# DAC.net
KiCad netlist of a schematic drawn in Altium Designer
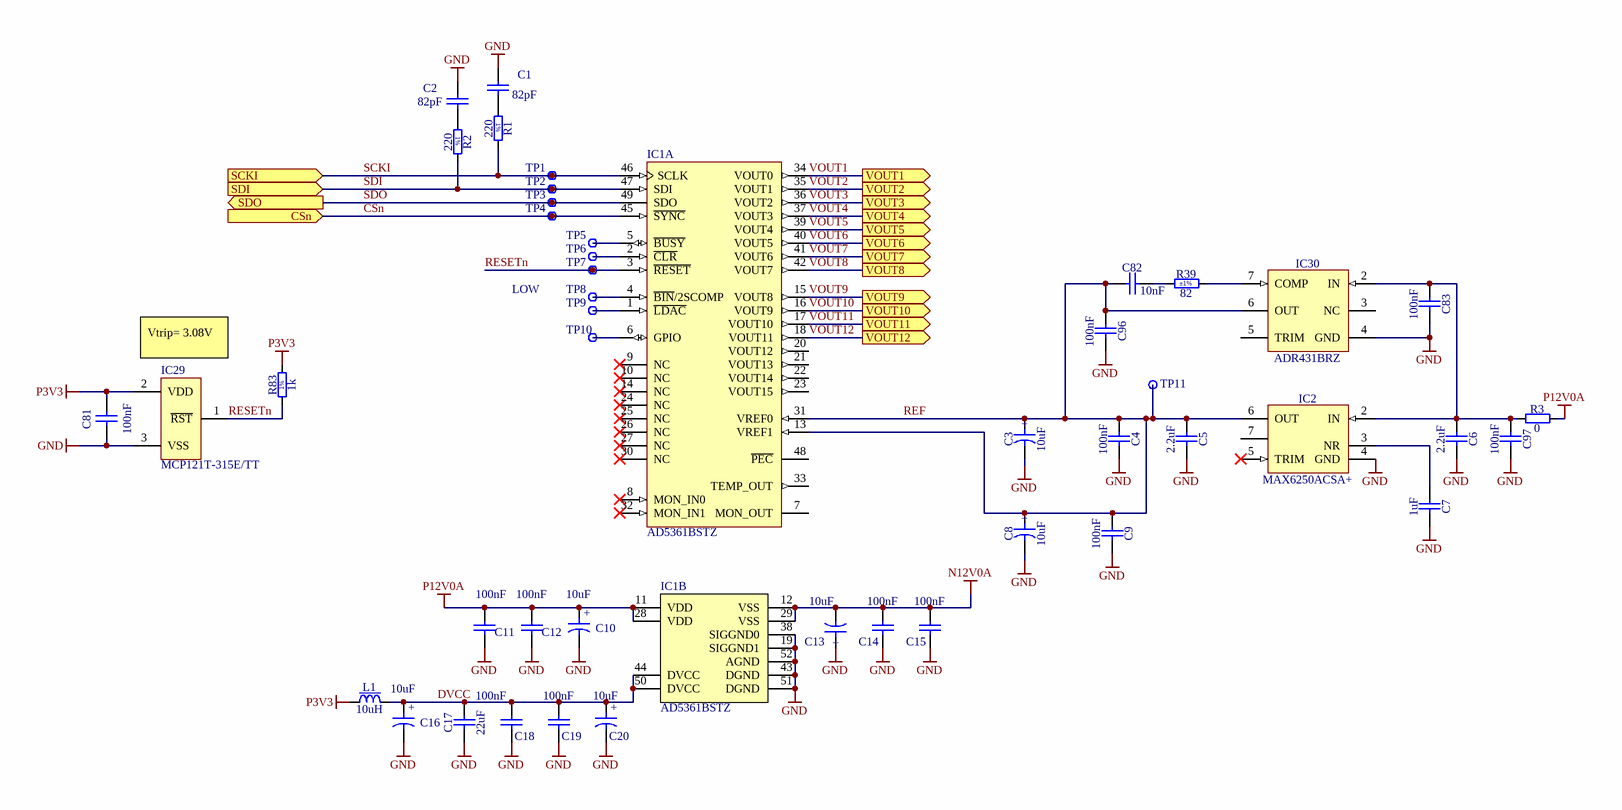
[diagram p0: DAC.SchDoc]

(export (version "E")
  (design (tool "Eeschema 10.0.6"))
  (components
    (comp (ref "C1")
      (value "82pF")
      (footprint "CAPC1608X87N")
      (description "Non-polarised capacitor")
      (fields
        (field (name "PART NUMBER") "CC0603_82PF_50V_5%_NP0")
        (field (name "VOLTAGE") "50V")
        (field (name "AUTHOR") "CERN DEM JLC")
      )
      (libsource (lib "Capacitors") (part "Capacitor - non polarized"))
    )
    (comp (ref "C2")
      (value "82pF")
      (footprint "CAPC1608X87N")
      (description "Non-polarised capacitor")
      (fields
        (field (name "PART NUMBER") "CC0603_82PF_50V_5%_NP0")
        (field (name "VOLTAGE") "50V")
        (field (name "AUTHOR") "CERN DEM JLC")
      )
      (libsource (lib "Capacitors") (part "Capacitor - non polarized"))
    )
    (comp (ref "C3")
      (value "10uF")
      (footprint "CAPMP3216X180N")
      (description "Polarised capacitor")
      (fields
        (field (name "PART NUMBER") "CTE3216-18_10UF_16V_20%_AVX_TCJ")
        (field (name "VOLTAGE") "16V")
        (field (name "AUTHOR") "CERN DEM JLC")
      )
      (libsource (lib "Capacitors") (part "Capacitor - polarized"))
    )
    (comp (ref "C4")
      (value "100nF")
      (footprint "CAPC1005X55N")
      (description "Non-polarised capacitor")
      (fields
        (field (name "PART NUMBER") "CC0402_100NF_16V_10%_X7R")
        (field (name "VOLTAGE") "16V")
        (field (name "AUTHOR") "CERN DEM JLC")
      )
      (libsource (lib "Capacitors") (part "Capacitor - non polarized"))
    )
    (comp (ref "C5")
      (value "2.2uF")
      (footprint "CAPC1608X87N")
      (description "Non-polarised capacitor")
      (fields
        (field (name "PART NUMBER") "CC0603_2.2UF_16V_10%_X5R")
        (field (name "VOLTAGE") "16V")
        (field (name "AUTHOR") "CERN DEM JLC")
      )
      (libsource (lib "Capacitors") (part "Capacitor - non polarized"))
    )
    (comp (ref "C6")
      (value "2.2uF")
      (footprint "CAPC1608X87N")
      (description "Non-polarised capacitor")
      (fields
        (field (name "PART NUMBER") "CC0603_2.2UF_16V_10%_X5R")
        (field (name "VOLTAGE") "16V")
        (field (name "AUTHOR") "CERN DEM JLC")
      )
      (libsource (lib "Capacitors") (part "Capacitor - non polarized"))
    )
    (comp (ref "C7")
      (value "1uF")
      (footprint "CAPC1608X87N")
      (description "Non-polarised capacitor")
      (fields
        (field (name "PART NUMBER") "CC0603_1UF_25V_10%_X7R")
        (field (name "VOLTAGE") "25V")
        (field (name "AUTHOR") "CERN DEM JLC")
      )
      (libsource (lib "Capacitors") (part "Capacitor - non polarized"))
    )
    (comp (ref "C8")
      (value "10uF")
      (footprint "CAPMP3216X180N")
      (description "Polarised capacitor")
      (fields
        (field (name "PART NUMBER") "CTE3216-18_10UF_16V_20%_AVX_TCJ")
        (field (name "VOLTAGE") "16V")
        (field (name "AUTHOR") "CERN DEM JLC")
      )
      (libsource (lib "Capacitors") (part "Capacitor - polarized"))
    )
    (comp (ref "C9")
      (value "100nF")
      (footprint "CAPC1005X55N")
      (description "Non-polarised capacitor")
      (fields
        (field (name "PART NUMBER") "CC0402_100NF_16V_10%_X7R")
        (field (name "VOLTAGE") "16V")
        (field (name "AUTHOR") "CERN DEM JLC")
      )
      (libsource (lib "Capacitors") (part "Capacitor - non polarized"))
    )
    (comp (ref "C10")
      (value "10uF")
      (footprint "CAPMP3216X180N")
      (description "Polarised capacitor")
      (fields
        (field (name "PART NUMBER") "CTE3216-18_10UF_16V_20%_AVX_TCJ")
        (field (name "VOLTAGE") "16V")
        (field (name "AUTHOR") "CERN DEM JLC")
      )
      (libsource (lib "") (part "Capacitor - polarized_1"))
    )
    (comp (ref "C11")
      (value "100nF")
      (footprint "CAPC1005X55N")
      (description "Non-polarised capacitor")
      (fields
        (field (name "PART NUMBER") "CC0402_100NF_16V_10%_X7R")
        (field (name "VOLTAGE") "16V")
        (field (name "AUTHOR") "CERN DEM JLC")
      )
      (libsource (lib "Capacitors") (part "Capacitor - non polarized"))
    )
    (comp (ref "C12")
      (value "100nF")
      (footprint "CAPC1005X55N")
      (description "Non-polarised capacitor")
      (fields
        (field (name "PART NUMBER") "CC0402_100NF_16V_10%_X7R")
        (field (name "VOLTAGE") "16V")
        (field (name "AUTHOR") "CERN DEM JLC")
      )
      (libsource (lib "Capacitors") (part "Capacitor - non polarized"))
    )
    (comp (ref "C13")
      (value "10uF")
      (footprint "CAPMP3216X180N")
      (description "Polarised capacitor")
      (fields
        (field (name "PART NUMBER") "CTE3216-18_10UF_16V_20%_AVX_TCJ")
        (field (name "VOLTAGE") "16V")
        (field (name "AUTHOR") "CERN DEM JLC")
      )
      (libsource (lib "Capacitors") (part "Capacitor - polarized"))
    )
    (comp (ref "C14")
      (value "100nF")
      (footprint "CAPC1005X55N")
      (description "Non-polarised capacitor")
      (fields
        (field (name "PART NUMBER") "CC0402_100NF_16V_10%_X7R")
        (field (name "VOLTAGE") "16V")
        (field (name "AUTHOR") "CERN DEM JLC")
      )
      (libsource (lib "Capacitors") (part "Capacitor - non polarized"))
    )
    (comp (ref "C15")
      (value "100nF")
      (footprint "CAPC1005X55N")
      (description "Non-polarised capacitor")
      (fields
        (field (name "PART NUMBER") "CC0402_100NF_16V_10%_X7R")
        (field (name "VOLTAGE") "16V")
        (field (name "AUTHOR") "CERN DEM JLC")
      )
      (libsource (lib "Capacitors") (part "Capacitor - non polarized"))
    )
    (comp (ref "C16")
      (value "10uF")
      (footprint "CAPMP3216X180N")
      (description "Polarised capacitor")
      (fields
        (field (name "PART NUMBER") "CTE3216-18_10UF_16V_20%_AVX_TCJ")
        (field (name "VOLTAGE") "16V")
        (field (name "AUTHOR") "CERN DEM JLC")
      )
      (libsource (lib "") (part "Capacitor - polarized_1"))
    )
    (comp (ref "C17")
      (value "22uF")
      (footprint "CAPC2012X135N")
      (description "Non-polarised capacitor")
      (fields
        (field (name "PART NUMBER") "CC0805_22UF_16V_10%_X5R")
        (field (name "VOLTAGE") "16V")
        (field (name "AUTHOR") "CERN DEM JLC")
      )
      (libsource (lib "Capacitors") (part "Capacitor - non polarized"))
    )
    (comp (ref "C18")
      (value "100nF")
      (footprint "CAPC1005X55N")
      (description "Non-polarised capacitor")
      (fields
        (field (name "PART NUMBER") "CC0402_100NF_16V_10%_X7R")
        (field (name "VOLTAGE") "16V")
        (field (name "AUTHOR") "CERN DEM JLC")
      )
      (libsource (lib "Capacitors") (part "Capacitor - non polarized"))
    )
    (comp (ref "C19")
      (value "100nF")
      (footprint "CAPC1005X55N")
      (description "Non-polarised capacitor")
      (fields
        (field (name "PART NUMBER") "CC0402_100NF_16V_10%_X7R")
        (field (name "VOLTAGE") "16V")
        (field (name "AUTHOR") "CERN DEM JLC")
      )
      (libsource (lib "Capacitors") (part "Capacitor - non polarized"))
    )
    (comp (ref "C20")
      (value "10uF")
      (footprint "CAPMP3216X180N")
      (description "Polarised capacitor")
      (fields
        (field (name "PART NUMBER") "CTE3216-18_10UF_16V_20%_AVX_TCJ")
        (field (name "VOLTAGE") "16V")
        (field (name "AUTHOR") "CERN DEM JLC")
      )
      (libsource (lib "") (part "Capacitor - polarized_1"))
    )
    (comp (ref "C81")
      (value "100nF")
      (footprint "CAPC1005X55N")
      (description "Non-polarised capacitor")
      (fields
        (field (name "PART NUMBER") "CC0402_100NF_16V_10%_X7R")
        (field (name "VOLTAGE") "16V")
        (field (name "AUTHOR") "CERN DEM JLC")
      )
      (libsource (lib "Capacitors") (part "Capacitor - non polarized"))
    )
    (comp (ref "C82")
      (value "10nF")
      (footprint "CAPC1005X55N")
      (description "Non-polarised capacitor")
      (fields
        (field (name "PART NUMBER") "CC0402_10NF_16V_10%_X7R")
        (field (name "VOLTAGE") "16V")
        (field (name "AUTHOR") "CERN DEM JLC")
      )
      (libsource (lib "Capacitors") (part "Capacitor - non polarized"))
    )
    (comp (ref "C83")
      (value "100nF")
      (footprint "CAPC1005X55N")
      (description "Non-polarised capacitor")
      (fields
        (field (name "PART NUMBER") "CC0402_100NF_16V_10%_X7R")
        (field (name "VOLTAGE") "16V")
        (field (name "AUTHOR") "CERN DEM JLC")
      )
      (libsource (lib "Capacitors") (part "Capacitor - non polarized"))
    )
    (comp (ref "C96")
      (value "100nF")
      (footprint "CAPC1005X55N")
      (description "Non-polarised capacitor")
      (fields
        (field (name "PART NUMBER") "CC0402_100NF_16V_10%_X7R")
        (field (name "VOLTAGE") "16V")
        (field (name "AUTHOR") "CERN DEM JLC")
      )
      (libsource (lib "Capacitors") (part "Capacitor - non polarized"))
    )
    (comp (ref "C97")
      (value "100nF")
      (footprint "CAPC1005X55N")
      (description "Non-polarised capacitor")
      (fields
        (field (name "PART NUMBER") "CC0402_100NF_16V_10%_X7R")
        (field (name "VOLTAGE") "16V")
        (field (name "AUTHOR") "CERN DEM JLC")
      )
      (libsource (lib "Capacitors") (part "Capacitor - non polarized"))
    )
    (comp (ref "IC1")
      (value "AD5361BSTZ")
      (footprint "ST-52_N")
      (description "14-Bit Digital-to-Analog Converter with Serial Interface, -40 to +85 degC, ST-52, Pb-Free, Tray")
      (fields (field (name "GENERIC PART NUMBER") "AD5361") (field (name "MANUFACTURER") "Analog Devices"))
      (libsource (lib "Altium Content Vault") (part "ADI-AD5361-ST-52"))
    )
    (comp (ref "IC2")
      (value "MAX6250ACSA+")
      (footprint "SOIC127P600X175-8N")
      (description "1ppm/°C, Low-Noise, Precision, +5.000V Voltage Reference")
      (fields (field (name "MANUFACTURER") "MAXIM") (field (name "AUTHOR") "CERN DEM JMW"))
      (libsource (lib "ICs And Semiconductors") (part "MAX6250"))
    )
    (comp (ref "IC29")
      (value "MCP121T-315E/TT")
      (footprint "SOT-23-TT3_L")
      (description "Micropower Voltage Supervisors, 3-Pin SOT-23, Extended Temperature, Tape and Reel")
      (libsource (lib "Altium Content Vault") (part "PM-SCCT-MCP121-3"))
    )
    (comp (ref "IC30")
      (value "ADR431BRZ")
      (footprint "SOIC127P600X175-8N")
      (fields
        (field (name "MANUFACTURER") "ANALOG DEVICES")
        (field (name "MANUFACTURER PART NUMBER") "ADR431BR")
        (field (name "AUTHOR") "CERN DEM JLC")
      )
      (libsource (lib "ICs And Semiconductors") (part "ADR431"))
    )
    (comp (ref "L1")
      (value "10uH")
      (footprint "IND_MURATA-PS_8400")
      (description "Inductor With Core")
      (fields
        (field (name "PART NUMBER") "IND_10UH_10%_MURATA-PS_8400")
        (field (name "POWER") "950mA")
        (field (name "AUTHOR") "CERN DEM JLC")
      )
      (libsource (lib "Inductors & Transformers") (part "Inductor With Magnetic core"))
    )
    (comp (ref "R1")
      (value "220")
      (footprint "RESC1608X55N")
      (description "Resistor - 1%")
      (fields
        (field (name "PART NUMBER") "R0603_220R_1%_0.1W_100PPM")
        (field (name "POWER") "0.1W")
        (field (name "AUTHOR") "CERN DEM JLC")
      )
      (libsource (lib "Resistors") (part "Resistor - 1%"))
    )
    (comp (ref "R2")
      (value "220")
      (footprint "RESC1608X55N")
      (description "Resistor - 1%")
      (fields
        (field (name "PART NUMBER") "R0603_220R_1%_0.1W_100PPM")
        (field (name "POWER") "0.1W")
        (field (name "AUTHOR") "CERN DEM JLC")
      )
      (libsource (lib "Resistors") (part "Resistor - 1%"))
    )
    (comp (ref "R3")
      (value "0")
      (footprint "RESC1005X40N")
      (description "Resistor")
      (fields
        (field (name "PART NUMBER") "R0402_0R_JUMPER")
        (field (name "MANUFACTURER") "GENERIC")
        (field (name "AUTHOR") "CERN DEM JLC")
      )
      (libsource (lib "Resistors") (part "Resistor"))
    )
    (comp (ref "R39")
      (value "82")
      (footprint "RESC1005X40N")
      (description "Resistor - 1%")
      (fields
        (field (name "TOLERANCE") "±1%")
        (field (name "PART NUMBER") "R0402_82R_1%_0.0625W_100PPM")
        (field (name "POWER") "0.0625W")
        (field (name "AUTHOR") "CERN DEM JLC")
      )
      (libsource (lib "Resistors") (part "Resistor - 1%"))
    )
    (comp (ref "R83")
      (value "1k")
      (footprint "RESC1005X40N")
      (description "Resistor - 1%")
      (fields
        (field (name "PART NUMBER") "R0402_1K_1%_0.0625W_100PPM")
        (field (name "POWER") "0.0625W")
        (field (name "AUTHOR") "CERN DEM JLC")
      )
      (libsource (lib "Resistors") (part "Resistor - 1%"))
    )
    (comp (ref "TP1")
      (value "Test Point")
      (footprint "TPS127")
      (fields (field (name "PART NUMBER") "SMD_PAD_1.27X1.27MM") (field (name "AUTHOR") "CERN DEM JLC"))
      (libsource (lib "Eletro-mechanical") (part "Test Point"))
    )
    (comp (ref "TP2")
      (value "Test Point")
      (footprint "TPS127")
      (fields (field (name "PART NUMBER") "SMD_PAD_1.27X1.27MM") (field (name "AUTHOR") "CERN DEM JLC"))
      (libsource (lib "Eletro-mechanical") (part "Test Point"))
    )
    (comp (ref "TP3")
      (value "Test Point")
      (footprint "TPS127")
      (fields (field (name "PART NUMBER") "SMD_PAD_1.27X1.27MM") (field (name "AUTHOR") "CERN DEM JLC"))
      (libsource (lib "Eletro-mechanical") (part "Test Point"))
    )
    (comp (ref "TP4")
      (value "Test Point")
      (footprint "TPS127")
      (fields (field (name "PART NUMBER") "SMD_PAD_1.27X1.27MM") (field (name "AUTHOR") "CERN DEM JLC"))
      (libsource (lib "Eletro-mechanical") (part "Test Point"))
    )
    (comp (ref "TP5")
      (value "Test Point")
      (footprint "TPS127")
      (fields (field (name "PART NUMBER") "SMD_PAD_1.27X1.27MM") (field (name "AUTHOR") "CERN DEM JLC"))
      (libsource (lib "Eletro-mechanical") (part "Test Point"))
    )
    (comp (ref "TP6")
      (value "Test Point")
      (footprint "TPS127")
      (fields (field (name "PART NUMBER") "SMD_PAD_1.27X1.27MM") (field (name "AUTHOR") "CERN DEM JLC"))
      (libsource (lib "Eletro-mechanical") (part "Test Point"))
    )
    (comp (ref "TP7")
      (value "Test Point")
      (footprint "TPS127")
      (fields (field (name "PART NUMBER") "SMD_PAD_1.27X1.27MM") (field (name "AUTHOR") "CERN DEM JLC"))
      (libsource (lib "Eletro-mechanical") (part "Test Point"))
    )
    (comp (ref "TP8")
      (value "Test Point")
      (footprint "TPS127")
      (fields (field (name "PART NUMBER") "SMD_PAD_1.27X1.27MM") (field (name "AUTHOR") "CERN DEM JLC"))
      (libsource (lib "Eletro-mechanical") (part "Test Point"))
    )
    (comp (ref "TP9")
      (value "Test Point")
      (footprint "TPS127")
      (fields (field (name "PART NUMBER") "SMD_PAD_1.27X1.27MM") (field (name "AUTHOR") "CERN DEM JLC"))
      (libsource (lib "Eletro-mechanical") (part "Test Point"))
    )
    (comp (ref "TP10")
      (value "Test Point")
      (footprint "TPS127")
      (fields (field (name "PART NUMBER") "SMD_PAD_1.27X1.27MM") (field (name "AUTHOR") "CERN DEM JLC"))
      (libsource (lib "Eletro-mechanical") (part "Test Point"))
    )
    (comp (ref "TP11")
      (value "Test Point")
      (footprint "TPS127")
      (fields (field (name "PART NUMBER") "SMD_PAD_1.27X1.27MM") (field (name "AUTHOR") "CERN DEM JLC"))
      (libsource (lib "Eletro-mechanical") (part "Test Point"))
    )
  )
  (nets
    (net (code "1") (name "/CSn") (class "Default")
      (node (ref "IC1") (pin "45") (pinfunction "~{SYNC}_45") (pintype "input"))
      (node (ref "TP4") (pin "1") (pinfunction "1_1") (pintype "bidirectional"))
    )
    (net (code "2") (name "/DVCC") (class "Default")
      (node (ref "C16") (pin "1") (pinfunction "1_1") (pintype "passive"))
      (node (ref "C17") (pin "2") (pinfunction "2_2") (pintype "passive"))
      (node (ref "C18") (pin "2") (pinfunction "2_2") (pintype "passive"))
      (node (ref "C19") (pin "2") (pinfunction "2_2") (pintype "passive"))
      (node (ref "C20") (pin "1") (pinfunction "1_1") (pintype "passive"))
      (node (ref "IC1") (pin "44") (pinfunction "DVCC_44") (pintype "power_in"))
      (node (ref "IC1") (pin "50") (pinfunction "DVCC_50") (pintype "power_in"))
      (node (ref "L1") (pin "2") (pinfunction "2_2") (pintype "passive"))
    )
    (net (code "3") (name "/REF") (class "Default")
      (node (ref "C3") (pin "1") (pinfunction "1_1") (pintype "passive"))
      (node (ref "C4") (pin "2") (pinfunction "2_2") (pintype "passive"))
      (node (ref "C5") (pin "2") (pinfunction "2_2") (pintype "passive"))
      (node (ref "C8") (pin "1") (pinfunction "1_1") (pintype "passive"))
      (node (ref "C82") (pin "1") (pinfunction "1_1") (pintype "passive"))
      (node (ref "C9") (pin "2") (pinfunction "2_2") (pintype "passive"))
      (node (ref "C96") (pin "2") (pinfunction "2_2") (pintype "passive"))
      (node (ref "IC1") (pin "13") (pinfunction "VREF1_13") (pintype "input"))
      (node (ref "IC1") (pin "31") (pinfunction "VREF0_31") (pintype "input"))
      (node (ref "IC2") (pin "6") (pinfunction "OUT_6") (pintype "power_in"))
      (node (ref "IC30") (pin "6") (pinfunction "OUT_6") (pintype "power_in"))
      (node (ref "TP11") (pin "1") (pinfunction "1_1") (pintype "bidirectional"))
    )
    (net (code "4") (name "/RESETn") (class "Default")
      (node (ref "IC1") (pin "3") (pinfunction "~{RESET}_3") (pintype "input"))
      (node (ref "IC29") (pin "1") (pinfunction "~{RST}_1") (pintype "open_collector"))
      (node (ref "R83") (pin "1") (pinfunction "1_1") (pintype "passive"))
      (node (ref "TP7") (pin "1") (pinfunction "1_1") (pintype "bidirectional"))
    )
    (net (code "5") (name "/SCKI") (class "Default")
      (node (ref "IC1") (pin "46") (pinfunction "SCLK_46") (pintype "input"))
      (node (ref "R1") (pin "2") (pinfunction "2_2") (pintype "passive"))
      (node (ref "TP1") (pin "1") (pinfunction "1_1") (pintype "bidirectional"))
    )
    (net (code "6") (name "/SDI") (class "Default")
      (node (ref "IC1") (pin "47") (pinfunction "SDI_47") (pintype "input"))
      (node (ref "R2") (pin "2") (pinfunction "2_2") (pintype "passive"))
      (node (ref "TP2") (pin "1") (pinfunction "1_1") (pintype "bidirectional"))
    )
    (net (code "7") (name "/SDO") (class "Default")
      (node (ref "IC1") (pin "49") (pinfunction "SDO_49") (pintype "tri_state"))
      (node (ref "TP3") (pin "1") (pinfunction "1_1") (pintype "bidirectional"))
    )
    (net (code "8") (name "/VOUT1") (class "Default")
      (node (ref "IC1") (pin "34") (pinfunction "VOUT0_34") (pintype "output"))
    )
    (net (code "9") (name "/VOUT2") (class "Default")
      (node (ref "IC1") (pin "35") (pinfunction "VOUT1_35") (pintype "output"))
    )
    (net (code "10") (name "/VOUT3") (class "Default")
      (node (ref "IC1") (pin "36") (pinfunction "VOUT2_36") (pintype "output"))
    )
    (net (code "11") (name "/VOUT4") (class "Default")
      (node (ref "IC1") (pin "37") (pinfunction "VOUT3_37") (pintype "output"))
    )
    (net (code "12") (name "/VOUT5") (class "Default")
      (node (ref "IC1") (pin "39") (pinfunction "VOUT4_39") (pintype "output"))
    )
    (net (code "13") (name "/VOUT6") (class "Default")
      (node (ref "IC1") (pin "40") (pinfunction "VOUT5_40") (pintype "output"))
    )
    (net (code "14") (name "/VOUT7") (class "Default")
      (node (ref "IC1") (pin "41") (pinfunction "VOUT6_41") (pintype "output"))
    )
    (net (code "15") (name "/VOUT8") (class "Default")
      (node (ref "IC1") (pin "42") (pinfunction "VOUT7_42") (pintype "output"))
    )
    (net (code "16") (name "/VOUT9") (class "Default")
      (node (ref "IC1") (pin "15") (pinfunction "VOUT8_15") (pintype "output"))
    )
    (net (code "17") (name "/VOUT10") (class "Default")
      (node (ref "IC1") (pin "16") (pinfunction "VOUT9_16") (pintype "output"))
    )
    (net (code "18") (name "/VOUT11") (class "Default")
      (node (ref "IC1") (pin "17") (pinfunction "VOUT10_17") (pintype "output"))
    )
    (net (code "19") (name "/VOUT12") (class "Default")
      (node (ref "IC1") (pin "18") (pinfunction "VOUT11_18") (pintype "output"))
    )
    (net (code "20") (name "GND") (class "Default")
      (node (ref "C1") (pin "1") (pinfunction "1_1") (pintype "passive"))
      (node (ref "C10") (pin "2") (pinfunction "2_2") (pintype "passive"))
      (node (ref "C11") (pin "1") (pinfunction "1_1") (pintype "passive"))
      (node (ref "C12") (pin "1") (pinfunction "1_1") (pintype "passive"))
      (node (ref "C13") (pin "1") (pinfunction "1_1") (pintype "passive"))
      (node (ref "C14") (pin "1") (pinfunction "1_1") (pintype "passive"))
      (node (ref "C15") (pin "1") (pinfunction "1_1") (pintype "passive"))
      (node (ref "C16") (pin "2") (pinfunction "2_2") (pintype "passive"))
      (node (ref "C17") (pin "1") (pinfunction "1_1") (pintype "passive"))
      (node (ref "C18") (pin "1") (pinfunction "1_1") (pintype "passive"))
      (node (ref "C19") (pin "1") (pinfunction "1_1") (pintype "passive"))
      (node (ref "C2") (pin "1") (pinfunction "1_1") (pintype "passive"))
      (node (ref "C20") (pin "2") (pinfunction "2_2") (pintype "passive"))
      (node (ref "C3") (pin "2") (pinfunction "2_2") (pintype "passive"))
      (node (ref "C4") (pin "1") (pinfunction "1_1") (pintype "passive"))
      (node (ref "C5") (pin "1") (pinfunction "1_1") (pintype "passive"))
      (node (ref "C6") (pin "1") (pinfunction "1_1") (pintype "passive"))
      (node (ref "C7") (pin "1") (pinfunction "1_1") (pintype "passive"))
      (node (ref "C8") (pin "2") (pinfunction "2_2") (pintype "passive"))
      (node (ref "C81") (pin "1") (pinfunction "1_1") (pintype "passive"))
      (node (ref "C83") (pin "1") (pinfunction "1_1") (pintype "passive"))
      (node (ref "C9") (pin "1") (pinfunction "1_1") (pintype "passive"))
      (node (ref "C96") (pin "1") (pinfunction "1_1") (pintype "passive"))
      (node (ref "C97") (pin "1") (pinfunction "1_1") (pintype "passive"))
      (node (ref "IC1") (pin "19") (pinfunction "SIGGND1_19") (pintype "power_in"))
      (node (ref "IC1") (pin "38") (pinfunction "SIGGND0_38") (pintype "power_in"))
      (node (ref "IC1") (pin "43") (pinfunction "DGND_43") (pintype "power_in"))
      (node (ref "IC1") (pin "51") (pinfunction "DGND_51") (pintype "power_in"))
      (node (ref "IC1") (pin "52") (pinfunction "AGND_52") (pintype "power_in"))
      (node (ref "IC2") (pin "4") (pinfunction "GND_4") (pintype "power_in"))
      (node (ref "IC29") (pin "3") (pinfunction "VSS_3") (pintype "power_in"))
      (node (ref "IC30") (pin "4") (pinfunction "GND_4") (pintype "power_in"))
    )
    (net (code "21") (name "N12V0A") (class "Default")
      (node (ref "C13") (pin "2") (pinfunction "2_2") (pintype "passive"))
      (node (ref "C14") (pin "2") (pinfunction "2_2") (pintype "passive"))
      (node (ref "C15") (pin "2") (pinfunction "2_2") (pintype "passive"))
      (node (ref "IC1") (pin "12") (pinfunction "VSS_12") (pintype "power_in"))
      (node (ref "IC1") (pin "29") (pinfunction "VSS_29") (pintype "power_in"))
    )
    (net (code "22") (name "Net-(C1-Pad2)") (class "Default")
      (node (ref "C1") (pin "2") (pinfunction "2_2") (pintype "passive"))
      (node (ref "R1") (pin "1") (pinfunction "1_1") (pintype "passive"))
    )
    (net (code "23") (name "Net-(C2-Pad2)") (class "Default")
      (node (ref "C2") (pin "2") (pinfunction "2_2") (pintype "passive"))
      (node (ref "R2") (pin "1") (pinfunction "1_1") (pintype "passive"))
    )
    (net (code "24") (name "Net-(C82-Pad2)") (class "Default")
      (node (ref "C82") (pin "2") (pinfunction "2_2") (pintype "passive"))
      (node (ref "R39") (pin "1") (pinfunction "1_1") (pintype "passive"))
    )
    (net (code "25") (name "Net-(IC1A-GPIO)") (class "Default")
      (node (ref "IC1") (pin "6") (pinfunction "GPIO_6") (pintype "bidirectional"))
      (node (ref "TP10") (pin "1") (pinfunction "1_1") (pintype "bidirectional"))
    )
    (net (code "26") (name "Net-(IC1A-~{BIN}{slash}2SCOMP)") (class "Default")
      (node (ref "IC1") (pin "4") (pinfunction "~{BIN}/2SCOMP_4") (pintype "input"))
      (node (ref "TP8") (pin "1") (pinfunction "1_1") (pintype "bidirectional"))
    )
    (net (code "27") (name "Net-(IC1A-~{BUSY})") (class "Default")
      (node (ref "IC1") (pin "5") (pinfunction "~{BUSY}_5") (pintype "bidirectional"))
      (node (ref "TP5") (pin "1") (pinfunction "1_1") (pintype "bidirectional"))
    )
    (net (code "28") (name "Net-(IC1A-~{CLR})") (class "Default")
      (node (ref "IC1") (pin "2") (pinfunction "~{CLR}_2") (pintype "input"))
      (node (ref "TP6") (pin "1") (pinfunction "1_1") (pintype "bidirectional"))
    )
    (net (code "29") (name "Net-(IC1A-~{LDAC})") (class "Default")
      (node (ref "IC1") (pin "1") (pinfunction "~{LDAC}_1") (pintype "input"))
      (node (ref "TP9") (pin "1") (pinfunction "1_1") (pintype "bidirectional"))
    )
    (net (code "30") (name "Net-(IC2-IN)") (class "Default")
      (node (ref "C6") (pin "2") (pinfunction "2_2") (pintype "passive"))
      (node (ref "C83") (pin "2") (pinfunction "2_2") (pintype "passive"))
      (node (ref "C97") (pin "2") (pinfunction "2_2") (pintype "passive"))
      (node (ref "IC2") (pin "2") (pinfunction "IN_2") (pintype "input"))
      (node (ref "IC30") (pin "2") (pinfunction "IN_2") (pintype "input"))
      (node (ref "R3") (pin "2") (pinfunction "2_2") (pintype "passive"))
    )
    (net (code "31") (name "Net-(IC2-NR)") (class "Default")
      (node (ref "C7") (pin "2") (pinfunction "2_2") (pintype "passive"))
      (node (ref "IC2") (pin "3") (pinfunction "NR_3") (pintype "passive"))
    )
    (net (code "32") (name "Net-(IC30-COMP)") (class "Default")
      (node (ref "IC30") (pin "7") (pinfunction "COMP_7") (pintype "input"))
      (node (ref "R39") (pin "2") (pinfunction "2_2") (pintype "passive"))
    )
    (net (code "33") (name "P3V3") (class "Default")
      (node (ref "C81") (pin "2") (pinfunction "2_2") (pintype "passive"))
      (node (ref "IC29") (pin "2") (pinfunction "VDD_2") (pintype "power_in"))
      (node (ref "L1") (pin "1") (pinfunction "1_1") (pintype "passive"))
      (node (ref "R83") (pin "2") (pinfunction "2_2") (pintype "passive"))
    )
    (net (code "34") (name "P12V0A") (class "Default")
      (node (ref "C10") (pin "1") (pinfunction "1_1") (pintype "passive"))
      (node (ref "C11") (pin "2") (pinfunction "2_2") (pintype "passive"))
      (node (ref "C12") (pin "2") (pinfunction "2_2") (pintype "passive"))
      (node (ref "IC1") (pin "11") (pinfunction "VDD_11") (pintype "power_in"))
      (node (ref "IC1") (pin "28") (pinfunction "VDD_28") (pintype "power_in"))
      (node (ref "R3") (pin "1") (pinfunction "1_1") (pintype "passive"))
    )
    (net (code "35") (name "unconnected-(IC1A-MON_IN0-Pad8)") (class "Default")
      (node (ref "IC1") (pin "8") (pinfunction "MON_IN0_8") (pintype "input+no_connect"))
    )
    (net (code "36") (name "unconnected-(IC1A-MON_IN1-Pad32)") (class "Default")
      (node (ref "IC1") (pin "32") (pinfunction "MON_IN1_32") (pintype "input+no_connect"))
    )
    (net (code "37") (name "unconnected-(IC1A-MON_OUT-Pad7)") (class "Default")
      (node (ref "IC1") (pin "7") (pinfunction "MON_OUT_7") (pintype "tri_state"))
    )
    (net (code "38") (name "unconnected-(IC1A-NC-Pad9)") (class "Default")
      (node (ref "IC1") (pin "9") (pinfunction "NC_9") (pintype "passive+no_connect"))
    )
    (net (code "39") (name "unconnected-(IC1A-NC-Pad10)") (class "Default")
      (node (ref "IC1") (pin "10") (pinfunction "NC_10") (pintype "passive+no_connect"))
    )
    (net (code "40") (name "unconnected-(IC1A-NC-Pad14)") (class "Default")
      (node (ref "IC1") (pin "14") (pinfunction "NC_14") (pintype "passive+no_connect"))
    )
    (net (code "41") (name "unconnected-(IC1A-NC-Pad24)") (class "Default")
      (node (ref "IC1") (pin "24") (pinfunction "NC_24") (pintype "passive+no_connect"))
    )
    (net (code "42") (name "unconnected-(IC1A-NC-Pad25)") (class "Default")
      (node (ref "IC1") (pin "25") (pinfunction "NC_25") (pintype "passive+no_connect"))
    )
    (net (code "43") (name "unconnected-(IC1A-NC-Pad26)") (class "Default")
      (node (ref "IC1") (pin "26") (pinfunction "NC_26") (pintype "passive+no_connect"))
    )
    (net (code "44") (name "unconnected-(IC1A-NC-Pad27)") (class "Default")
      (node (ref "IC1") (pin "27") (pinfunction "NC_27") (pintype "passive+no_connect"))
    )
    (net (code "45") (name "unconnected-(IC1A-NC-Pad30)") (class "Default")
      (node (ref "IC1") (pin "30") (pinfunction "NC_30") (pintype "passive+no_connect"))
    )
    (net (code "46") (name "unconnected-(IC1A-TEMP_OUT-Pad33)") (class "Default")
      (node (ref "IC1") (pin "33") (pinfunction "TEMP_OUT_33") (pintype "output"))
    )
    (net (code "47") (name "unconnected-(IC1A-VOUT12-Pad20)") (class "Default")
      (node (ref "IC1") (pin "20") (pinfunction "VOUT12_20") (pintype "output"))
    )
    (net (code "48") (name "unconnected-(IC1A-VOUT13-Pad21)") (class "Default")
      (node (ref "IC1") (pin "21") (pinfunction "VOUT13_21") (pintype "output"))
    )
    (net (code "49") (name "unconnected-(IC1A-VOUT14-Pad22)") (class "Default")
      (node (ref "IC1") (pin "22") (pinfunction "VOUT14_22") (pintype "output"))
    )
    (net (code "50") (name "unconnected-(IC1A-VOUT15-Pad23)") (class "Default")
      (node (ref "IC1") (pin "23") (pinfunction "VOUT15_23") (pintype "output"))
    )
    (net (code "51") (name "unconnected-(IC1A-~{PEC}-Pad48)") (class "Default")
      (node (ref "IC1") (pin "48") (pinfunction "~{PEC}_48") (pintype "open_collector"))
    )
    (net (code "52") (name "unconnected-(IC2-Pad7)") (class "Default")
      (node (ref "IC2") (pin "7") (pintype "passive"))
    )
    (net (code "53") (name "unconnected-(IC2-TRIM-Pad5)") (class "Default")
      (node (ref "IC2") (pin "5") (pinfunction "TRIM_5") (pintype "input+no_connect"))
    )
    (net (code "54") (name "unconnected-(IC30-NC-Pad3)") (class "Default")
      (node (ref "IC30") (pin "3") (pinfunction "NC_3") (pintype "passive"))
    )
    (net (code "55") (name "unconnected-(IC30-TRIM-Pad5)") (class "Default")
      (node (ref "IC30") (pin "5") (pinfunction "TRIM_5") (pintype "passive"))
    )
  )
)
